# Quadcopter_controller.net
KiCad netlist of a schematic drawn in Altium Designer
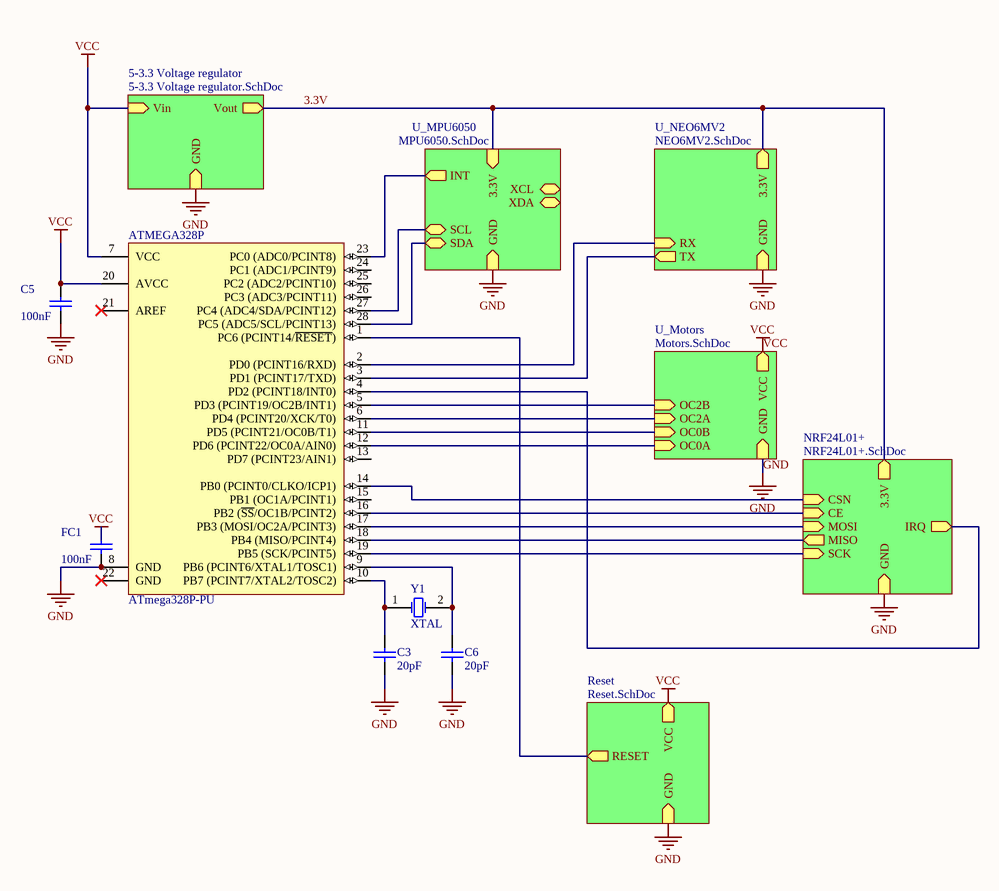
[diagram p0: Quadcopter_controller.SchDoc]

(export (version "E")
  (design (tool "Eeschema 10.0.6"))
  (components
    (comp (ref "ATMEGA328P")
      (value "ATmega328P-PU")
      (footprint "28P3")
      (libsource (lib "Atmel Microcontroller megaAVR") (part "ATmega328P-PU"))
    )
    (comp (ref "C3")
      (value "20pF")
      (footprint "RAD-0.3")
      (description "Capacitor")
      (fields (field (name "PUBLISHER") "Altium Limited"))
      (libsource (lib "Miscellaneous Devices") (part "Cap"))
    )
    (comp (ref "C5")
      (value "100nF")
      (footprint "RAD-0.3")
      (description "Capacitor")
      (fields (field (name "PUBLISHER") "Altium Limited"))
      (libsource (lib "Miscellaneous Devices") (part "Cap"))
    )
    (comp (ref "C6")
      (value "20pF")
      (footprint "RAD-0.3")
      (description "Capacitor")
      (fields (field (name "PUBLISHER") "Altium Limited"))
      (libsource (lib "Miscellaneous Devices") (part "Cap"))
    )
    (comp (ref "FC1")
      (value "100nF")
      (footprint "RAD-0.3")
      (description "Capacitor")
      (fields (field (name "PUBLISHER") "Altium Limited"))
      (libsource (lib "Miscellaneous Devices") (part "Cap"))
    )
    (comp (ref "Y1")
      (value "XTAL")
      (footprint "R38")
      (description "Crystal Oscillator")
      (fields (field (name "PUBLISHER") "Altium Limited"))
      (libsource (lib "Miscellaneous Devices") (part "XTAL"))
    )
  )
  (nets
    (net (code "2") (name "/CE") (class "Default")
      (node (ref "ATMEGA328P") (pin "16") (pinfunction "PB2_(~{SS}/OC1B/PCINT2)_16") (pintype "bidirectional"))
    )
    (net (code "3") (name "/CSN") (class "Default")
      (node (ref "ATMEGA328P") (pin "14") (pinfunction "PB0_(PCINT0/CLKO/ICP1)_14") (pintype "bidirectional"))
    )
    (net (code "4") (name "/INT") (class "Default")
      (node (ref "ATMEGA328P") (pin "23") (pinfunction "PC0_(ADC0/PCINT8)_23") (pintype "bidirectional"))
    )
    (net (code "5") (name "/IRQ") (class "Default")
      (node (ref "ATMEGA328P") (pin "4") (pinfunction "PD2_(PCINT18/INT0)_4") (pintype "bidirectional"))
    )
    (net (code "6") (name "/MISO") (class "Default")
      (node (ref "ATMEGA328P") (pin "18") (pinfunction "PB4_(MISO/PCINT4)_18") (pintype "bidirectional"))
    )
    (net (code "7") (name "/MOSI") (class "Default")
      (node (ref "ATMEGA328P") (pin "17") (pinfunction "PB3_(MOSI/OC2A/PCINT3)_17") (pintype "bidirectional"))
    )
    (net (code "8") (name "/OC0A") (class "Default")
      (node (ref "ATMEGA328P") (pin "12") (pinfunction "PD6_(PCINT22/OC0A/AIN0)_12") (pintype "bidirectional"))
    )
    (net (code "9") (name "/OC0B") (class "Default")
      (node (ref "ATMEGA328P") (pin "11") (pinfunction "PD5_(PCINT21/OC0B/T1)_11") (pintype "bidirectional"))
    )
    (net (code "10") (name "/OC2A") (class "Default")
      (node (ref "ATMEGA328P") (pin "6") (pinfunction "PD4_(PCINT20/XCK/T0)_6") (pintype "bidirectional"))
    )
    (net (code "11") (name "/OC2B") (class "Default")
      (node (ref "ATMEGA328P") (pin "5") (pinfunction "PD3_(PCINT19/OC2B/INT1)_5") (pintype "bidirectional"))
    )
    (net (code "12") (name "/RESET") (class "Default")
      (node (ref "ATMEGA328P") (pin "1") (pinfunction "PC6_(PCINT14/~{RESET})_1") (pintype "bidirectional"))
    )
    (net (code "13") (name "/RX") (class "Default")
      (node (ref "ATMEGA328P") (pin "2") (pinfunction "PD0_(PCINT16/RXD)_2") (pintype "bidirectional"))
    )
    (net (code "14") (name "/SCK") (class "Default")
      (node (ref "ATMEGA328P") (pin "19") (pinfunction "PB5_(SCK/PCINT5)_19") (pintype "bidirectional"))
    )
    (net (code "15") (name "/SCL") (class "Default")
      (node (ref "ATMEGA328P") (pin "27") (pinfunction "PC4_(ADC4/SDA/PCINT12)_27") (pintype "bidirectional"))
    )
    (net (code "16") (name "/SDA") (class "Default")
      (node (ref "ATMEGA328P") (pin "28") (pinfunction "PC5_(ADC5/SCL/PCINT13)_28") (pintype "bidirectional"))
    )
    (net (code "17") (name "/TX") (class "Default")
      (node (ref "ATMEGA328P") (pin "3") (pinfunction "PD1_(PCINT17/TXD)_3") (pintype "bidirectional"))
    )
    (net (code "20") (name "GND") (class "Default")
      (node (ref "ATMEGA328P") (pin "8") (pinfunction "GND_8") (pintype "power_in"))
      (node (ref "C3") (pin "1") (pinfunction "1_1") (pintype "passive"))
      (node (ref "C5") (pin "1") (pinfunction "1_1") (pintype "passive"))
      (node (ref "C6") (pin "1") (pinfunction "1_1") (pintype "passive"))
      (node (ref "FC1") (pin "1") (pinfunction "1_1") (pintype "passive"))
    )
    (net (code "21") (name "Net-(ATMEGA328P-PB6_(PCINT6{slash}XTAL1{slash}TOSC1))") (class "Default")
      (node (ref "ATMEGA328P") (pin "9") (pinfunction "PB6_(PCINT6/XTAL1/TOSC1)_9") (pintype "bidirectional"))
      (node (ref "C6") (pin "2") (pinfunction "2_2") (pintype "passive"))
      (node (ref "Y1") (pin "2") (pinfunction "OSC2_2") (pintype "passive"))
    )
    (net (code "22") (name "Net-(ATMEGA328P-PB7_(PCINT7{slash}XTAL2{slash}TOSC2))") (class "Default")
      (node (ref "ATMEGA328P") (pin "10") (pinfunction "PB7_(PCINT7/XTAL2/TOSC2)_10") (pintype "bidirectional"))
      (node (ref "C3") (pin "2") (pinfunction "2_2") (pintype "passive"))
      (node (ref "Y1") (pin "1") (pinfunction "OSC1_1") (pintype "passive"))
    )
    (net (code "23") (name "VCC") (class "Default")
      (node (ref "ATMEGA328P") (pin "20") (pinfunction "AVCC_20") (pintype "power_in"))
      (node (ref "ATMEGA328P") (pin "7") (pinfunction "VCC_7") (pintype "power_in"))
      (node (ref "C5") (pin "2") (pinfunction "2_2") (pintype "passive"))
      (node (ref "FC1") (pin "2") (pinfunction "2_2") (pintype "passive"))
    )
    (net (code "24") (name "unconnected-(ATMEGA328P-AREF-Pad21)") (class "Default")
      (node (ref "ATMEGA328P") (pin "21") (pinfunction "AREF_21") (pintype "power_in+no_connect"))
    )
    (net (code "25") (name "unconnected-(ATMEGA328P-GND-Pad22)") (class "Default")
      (node (ref "ATMEGA328P") (pin "22") (pinfunction "GND_22") (pintype "power_in+no_connect"))
    )
    (net (code "26") (name "unconnected-(ATMEGA328P-PB1_(OC1A{slash}PCINT1)-Pad15)") (class "Default")
      (node (ref "ATMEGA328P") (pin "15") (pinfunction "PB1_(OC1A/PCINT1)_15") (pintype "bidirectional"))
    )
    (net (code "27") (name "unconnected-(ATMEGA328P-PC1_(ADC1{slash}PCINT9)-Pad24)") (class "Default")
      (node (ref "ATMEGA328P") (pin "24") (pinfunction "PC1_(ADC1/PCINT9)_24") (pintype "bidirectional"))
    )
    (net (code "28") (name "unconnected-(ATMEGA328P-PC2_(ADC2{slash}PCINT10)-Pad25)") (class "Default")
      (node (ref "ATMEGA328P") (pin "25") (pinfunction "PC2_(ADC2/PCINT10)_25") (pintype "bidirectional"))
    )
    (net (code "29") (name "unconnected-(ATMEGA328P-PC3_(ADC3{slash}PCINT11)-Pad26)") (class "Default")
      (node (ref "ATMEGA328P") (pin "26") (pinfunction "PC3_(ADC3/PCINT11)_26") (pintype "bidirectional"))
    )
    (net (code "30") (name "unconnected-(ATMEGA328P-PD7_(PCINT23{slash}AIN1)-Pad13)") (class "Default")
      (node (ref "ATMEGA328P") (pin "13") (pinfunction "PD7_(PCINT23/AIN1)_13") (pintype "bidirectional"))
    )
  )
)
